# Teensy_board.net
KiCad netlist of a schematic drawn in EAGLE
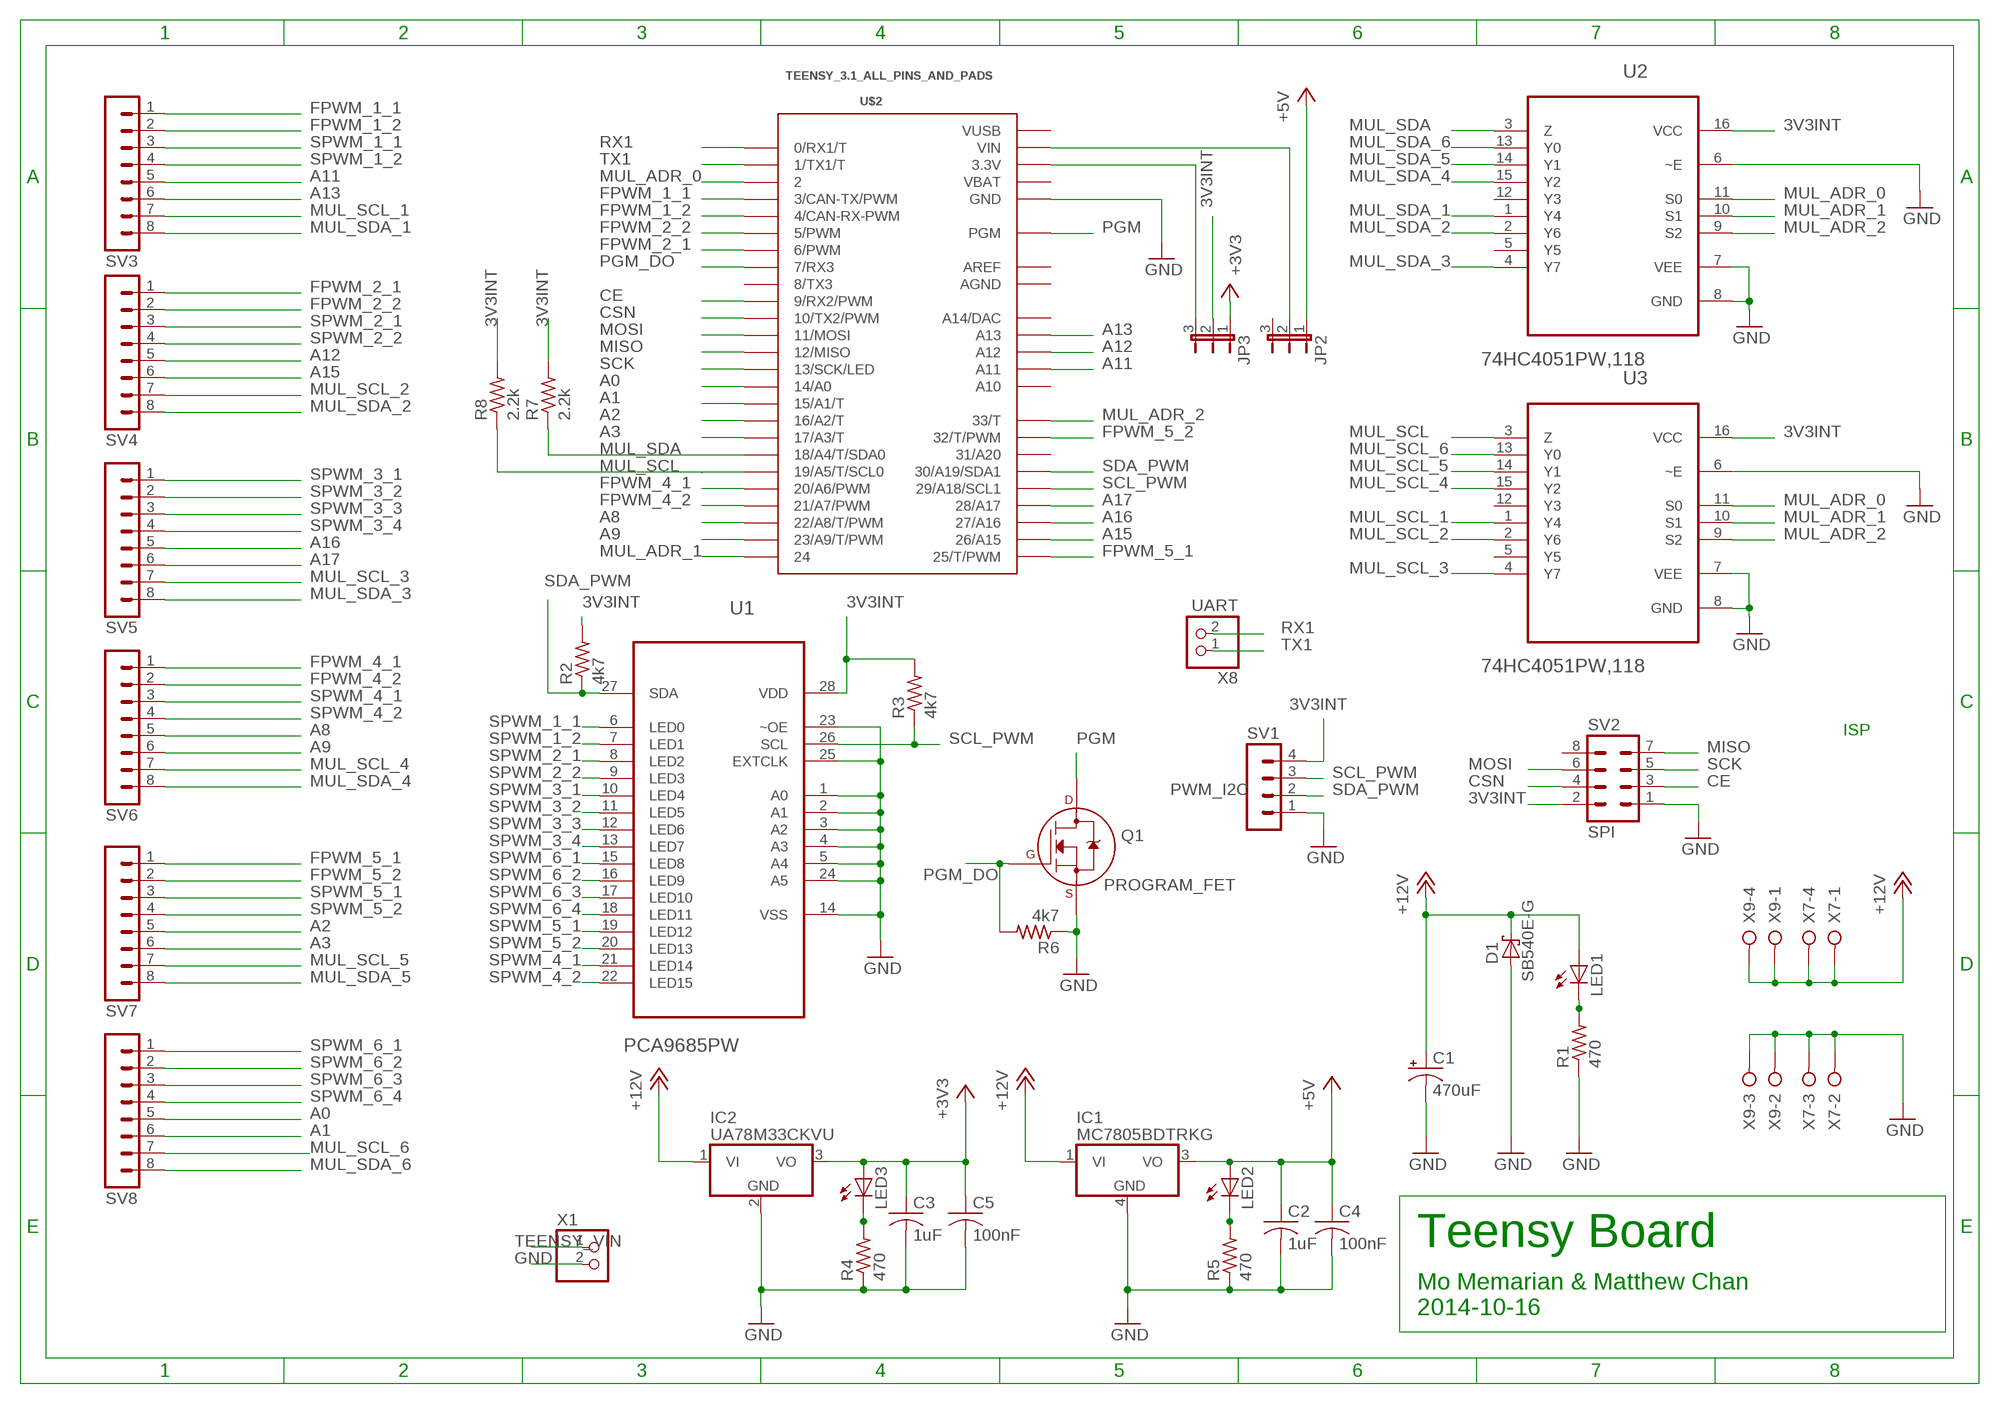
[diagram p0: schematic, sheet 1]

(export (version "E")
  (design (tool "Eeschema 10.0.6"))
  (components
    (comp (ref "C1")
      (value "470uF")
      (footprint "eagle-import:E5-10,5")
      (libsource (lib "eagle-import") (part "CPOL-USE5-10.5"))
    )
    (comp (ref "C2")
      (value "1uF")
      (footprint "eagle-import:C0603")
      (libsource (lib "eagle-import") (part "C-USC0603"))
    )
    (comp (ref "C3")
      (value "1uF")
      (footprint "eagle-import:C0603")
      (libsource (lib "eagle-import") (part "C-USC0603"))
    )
    (comp (ref "C4")
      (value "100nF")
      (footprint "eagle-import:C0603")
      (libsource (lib "eagle-import") (part "C-USC0603"))
    )
    (comp (ref "C5")
      (value "100nF")
      (footprint "eagle-import:C0603")
      (libsource (lib "eagle-import") (part "C-USC0603"))
    )
    (comp (ref "D1")
      (value "SB540E-G")
      (footprint "eagle-import:DO201T15")
      (libsource (lib "eagle-import") (part "SB540E-G"))
    )
    (comp (ref "IC1")
      (value "MC7805BDTRKG")
      (footprint "eagle-import:DPACK_3")
      (libsource (lib "eagle-import") (part "MC7805BDTRKG"))
    )
    (comp (ref "IC2")
      (value "UA78M33CKVU")
      (footprint "eagle-import:DPACK")
      (libsource (lib "eagle-import") (part "UA78MKVU33C"))
    )
    (comp (ref "JP2")
      (value "JP2E")
      (footprint "eagle-import:JP2")
      (libsource (lib "eagle-import") (part "JP2E"))
    )
    (comp (ref "JP3")
      (value "JP2E")
      (footprint "eagle-import:JP2")
      (libsource (lib "eagle-import") (part "JP2E"))
    )
    (comp (ref "LED1")
      (value "LEDSML1206")
      (footprint "eagle-import:SML1206")
      (libsource (lib "eagle-import") (part "LEDSML1206"))
    )
    (comp (ref "LED2")
      (value "LEDSML1206")
      (footprint "eagle-import:SML1206")
      (libsource (lib "eagle-import") (part "LEDSML1206"))
    )
    (comp (ref "LED3")
      (value "LEDSML1206")
      (footprint "eagle-import:SML1206")
      (libsource (lib "eagle-import") (part "LEDSML1206"))
    )
    (comp (ref "Q1")
      (value "PROGRAM_FET")
      (footprint "eagle-import:SOT-23")
      (libsource (lib "eagle-import") (part "2N700_SOT232"))
    )
    (comp (ref "R1")
      (value "470")
      (footprint "eagle-import:R0603")
      (libsource (lib "eagle-import") (part "R-US_R0603"))
    )
    (comp (ref "R2")
      (value "4k7")
      (footprint "eagle-import:R0603")
      (libsource (lib "eagle-import") (part "R-US_R0603"))
    )
    (comp (ref "R3")
      (value "4k7")
      (footprint "eagle-import:R0603")
      (libsource (lib "eagle-import") (part "R-US_R0603"))
    )
    (comp (ref "R4")
      (value "470")
      (footprint "eagle-import:R0603")
      (libsource (lib "eagle-import") (part "R-US_R0603"))
    )
    (comp (ref "R5")
      (value "470")
      (footprint "eagle-import:R0603")
      (libsource (lib "eagle-import") (part "R-US_R0603"))
    )
    (comp (ref "R6")
      (value "4k7")
      (footprint "eagle-import:R0603")
      (libsource (lib "eagle-import") (part "R-US_R0603"))
    )
    (comp (ref "R7")
      (value "2.2k")
      (footprint "eagle-import:R0603")
      (libsource (lib "eagle-import") (part "R-US_R0603"))
    )
    (comp (ref "R8")
      (value "2.2k")
      (footprint "eagle-import:R0603")
      (libsource (lib "eagle-import") (part "R-US_R0603"))
    )
    (comp (ref "SV1")
      (value "PWM_I2C")
      (footprint "eagle-import:MA04-1")
      (libsource (lib "eagle-import") (part "MA04-1"))
    )
    (comp (ref "SV2")
      (value "SPI")
      (footprint "eagle-import:MA04-2")
      (libsource (lib "eagle-import") (part "MA04-2"))
    )
    (comp (ref "SV3")
      (value "MA08-1")
      (footprint "eagle-import:MA08-1")
      (libsource (lib "eagle-import") (part "MA08-1"))
    )
    (comp (ref "SV4")
      (value "MA08-1")
      (footprint "eagle-import:MA08-1")
      (libsource (lib "eagle-import") (part "MA08-1"))
    )
    (comp (ref "SV5")
      (value "MA08-1")
      (footprint "eagle-import:MA08-1")
      (libsource (lib "eagle-import") (part "MA08-1"))
    )
    (comp (ref "SV6")
      (value "MA08-1")
      (footprint "eagle-import:MA08-1")
      (libsource (lib "eagle-import") (part "MA08-1"))
    )
    (comp (ref "SV7")
      (value "MA08-1")
      (footprint "eagle-import:MA08-1")
      (libsource (lib "eagle-import") (part "MA08-1"))
    )
    (comp (ref "SV8")
      (value "MA08-1")
      (footprint "eagle-import:MA08-1")
      (libsource (lib "eagle-import") (part "MA08-1"))
    )
    (comp (ref "U$2")
      (value "TEENSY_3.1_ALL_PINS_AND_PADS")
      (footprint "eagle-import:TEENSY_3.1_ALLPINS")
      (libsource (lib "eagle-import") (part "TEENSY_3.1_ALL_PINS_AND_PADS"))
    )
    (comp (ref "U1")
      (value "PCA9685PW")
      (footprint "eagle-import:SOP65P640X110-28N")
      (libsource (lib "eagle-import") (part "PCA9685PW"))
    )
    (comp (ref "U2")
      (value "74HC4051PW,118")
      (footprint "eagle-import:SOP65P640X110-16N")
      (libsource (lib "eagle-import") (part "74HC4051PW,118"))
    )
    (comp (ref "U3")
      (value "74HC4051PW,118")
      (footprint "eagle-import:SOP65P640X110-16N")
      (libsource (lib "eagle-import") (part "74HC4051PW,118"))
    )
    (comp (ref "X1")
      (value "PINHD-1X2")
      (footprint "eagle-import:1X02")
      (libsource (lib "eagle-import") (part "PINHD-1X2"))
    )
    (comp (ref "X7")
      (value "W237-04P")
      (footprint "eagle-import:W237-4P")
      (libsource (lib "eagle-import") (part "W237-04P"))
    )
    (comp (ref "X8")
      (value "UART")
      (footprint "eagle-import:1X02")
      (libsource (lib "eagle-import") (part "PINHD-1X2"))
    )
    (comp (ref "X9")
      (value "W237-04P")
      (footprint "eagle-import:W237-4P")
      (libsource (lib "eagle-import") (part "W237-04P"))
    )
  )
  (nets
    (net (code "1") (name "+3V3") (class "Default")
      (node (ref "C3") (pin "1") (pinfunction "1_1") (pintype "passive"))
      (node (ref "C5") (pin "1") (pinfunction "1_1") (pintype "passive"))
      (node (ref "IC2") (pin "3") (pinfunction "VO_3") (pintype "passive"))
      (node (ref "JP3") (pin "1") (pinfunction "1_1") (pintype "passive"))
      (node (ref "LED3") (pin "A") (pinfunction "A_A") (pintype "passive"))
    )
    (net (code "2") (name "+5V") (class "Default")
      (node (ref "C2") (pin "1") (pinfunction "1_1") (pintype "passive"))
      (node (ref "C4") (pin "1") (pinfunction "1_1") (pintype "passive"))
      (node (ref "IC1") (pin "3") (pinfunction "VO_3") (pintype "passive"))
      (node (ref "JP2") (pin "1") (pinfunction "1_1") (pintype "passive"))
      (node (ref "LED2") (pin "A") (pinfunction "A_A") (pintype "passive"))
    )
    (net (code "3") (name "+12V") (class "Default")
      (node (ref "C1") (pin "+") (pinfunction "+_+") (pintype "passive"))
      (node (ref "D1") (pin "C") (pinfunction "C_C") (pintype "passive"))
      (node (ref "IC1") (pin "1") (pinfunction "VI_1") (pintype "input"))
      (node (ref "IC2") (pin "1") (pinfunction "VI_1") (pintype "input"))
      (node (ref "LED1") (pin "A") (pinfunction "A_A") (pintype "passive"))
      (node (ref "X7") (pin "1") (pinfunction "KL_1") (pintype "passive"))
      (node (ref "X7") (pin "4") (pinfunction "KL_4") (pintype "passive"))
      (node (ref "X9") (pin "1") (pinfunction "KL_1") (pintype "passive"))
      (node (ref "X9") (pin "4") (pinfunction "KL_4") (pintype "passive"))
    )
    (net (code "4") (name "/3V3INT") (class "Default")
      (node (ref "JP3") (pin "2") (pinfunction "2_2") (pintype "passive"))
      (node (ref "R2") (pin "2") (pinfunction "2_2") (pintype "passive"))
      (node (ref "R3") (pin "2") (pinfunction "2_2") (pintype "passive"))
      (node (ref "R7") (pin "2") (pinfunction "2_2") (pintype "passive"))
      (node (ref "R8") (pin "2") (pinfunction "2_2") (pintype "passive"))
      (node (ref "SV1") (pin "4") (pinfunction "4_4") (pintype "passive"))
      (node (ref "SV2") (pin "2") (pinfunction "2_2") (pintype "passive"))
      (node (ref "U1") (pin "28") (pinfunction "VDD_28") (pintype "power_in"))
      (node (ref "U2") (pin "16") (pinfunction "VCC_16") (pintype "power_in"))
      (node (ref "U3") (pin "16") (pinfunction "VCC_16") (pintype "power_in"))
    )
    (net (code "5") (name "/A0") (class "Default")
      (node (ref "SV8") (pin "5") (pinfunction "5_5") (pintype "passive"))
      (node (ref "U$2") (pin "14/A0") (pinfunction "14/A0_14/A0") (pintype "bidirectional"))
    )
    (net (code "6") (name "/A1") (class "Default")
      (node (ref "SV8") (pin "6") (pinfunction "6_6") (pintype "passive"))
      (node (ref "U$2") (pin "15/A1") (pinfunction "15/A1/T_15/A1") (pintype "bidirectional"))
    )
    (net (code "7") (name "/A2") (class "Default")
      (node (ref "SV7") (pin "5") (pinfunction "5_5") (pintype "passive"))
      (node (ref "U$2") (pin "16/A2") (pinfunction "16/A2/T_16/A2") (pintype "bidirectional"))
    )
    (net (code "8") (name "/A3") (class "Default")
      (node (ref "SV7") (pin "6") (pinfunction "6_6") (pintype "passive"))
      (node (ref "U$2") (pin "17/A3") (pinfunction "17/A3/T_17/A3") (pintype "bidirectional"))
    )
    (net (code "9") (name "/A8") (class "Default")
      (node (ref "SV6") (pin "5") (pinfunction "5_5") (pintype "passive"))
      (node (ref "U$2") (pin "22/A8") (pinfunction "22/A8/T/PWM_22/A8") (pintype "bidirectional"))
    )
    (net (code "10") (name "/A9") (class "Default")
      (node (ref "SV6") (pin "6") (pinfunction "6_6") (pintype "passive"))
      (node (ref "U$2") (pin "23/A9") (pinfunction "23/A9/T/PWM_23/A9") (pintype "bidirectional"))
    )
    (net (code "11") (name "/A11") (class "Default")
      (node (ref "SV3") (pin "5") (pinfunction "5_5") (pintype "passive"))
      (node (ref "U$2") (pin "A11") (pinfunction "A11_A11") (pintype "bidirectional"))
    )
    (net (code "12") (name "/A12") (class "Default")
      (node (ref "SV4") (pin "5") (pinfunction "5_5") (pintype "passive"))
      (node (ref "U$2") (pin "A12") (pinfunction "A12_A12") (pintype "bidirectional"))
    )
    (net (code "13") (name "/A13") (class "Default")
      (node (ref "SV3") (pin "6") (pinfunction "6_6") (pintype "passive"))
      (node (ref "U$2") (pin "A13") (pinfunction "A13_A13") (pintype "bidirectional"))
    )
    (net (code "14") (name "/A15") (class "Default")
      (node (ref "SV4") (pin "6") (pinfunction "6_6") (pintype "passive"))
      (node (ref "U$2") (pin "26") (pinfunction "26/A15_26") (pintype "bidirectional"))
    )
    (net (code "15") (name "/A16") (class "Default")
      (node (ref "SV5") (pin "5") (pinfunction "5_5") (pintype "passive"))
      (node (ref "U$2") (pin "27") (pinfunction "27/A16_27") (pintype "bidirectional"))
    )
    (net (code "16") (name "/A17") (class "Default")
      (node (ref "SV5") (pin "6") (pinfunction "6_6") (pintype "passive"))
      (node (ref "U$2") (pin "28") (pinfunction "28/A17_28") (pintype "bidirectional"))
    )
    (net (code "17") (name "/AGND") (class "Default")
      (node (ref "U$2") (pin "AGND") (pinfunction "AGND_AGND") (pintype "power_in"))
    )
    (net (code "18") (name "/AREF") (class "Default")
      (node (ref "U$2") (pin "AREF") (pinfunction "AREF_AREF") (pintype "power_in"))
    )
    (net (code "19") (name "/CE") (class "Default")
      (node (ref "SV2") (pin "3") (pinfunction "3_3") (pintype "passive"))
      (node (ref "U$2") (pin "9") (pinfunction "9/RX2/PWM_9") (pintype "bidirectional"))
    )
    (net (code "20") (name "/CSN") (class "Default")
      (node (ref "SV2") (pin "4") (pinfunction "4_4") (pintype "passive"))
      (node (ref "U$2") (pin "10") (pinfunction "10/TX2/PWM_10") (pintype "bidirectional"))
    )
    (net (code "21") (name "/FPWM_1_1") (class "Default")
      (node (ref "SV3") (pin "1") (pinfunction "1_1") (pintype "passive"))
      (node (ref "U$2") (pin "3") (pinfunction "3/CAN-TX/PWM_3") (pintype "bidirectional"))
    )
    (net (code "22") (name "/FPWM_1_2") (class "Default")
      (node (ref "SV3") (pin "2") (pinfunction "2_2") (pintype "passive"))
      (node (ref "U$2") (pin "4") (pinfunction "4/CAN-RX-PWM_4") (pintype "bidirectional"))
    )
    (net (code "23") (name "/FPWM_2_1") (class "Default")
      (node (ref "SV4") (pin "1") (pinfunction "1_1") (pintype "passive"))
      (node (ref "U$2") (pin "6") (pinfunction "6/PWM_6") (pintype "bidirectional"))
    )
    (net (code "24") (name "/FPWM_2_2") (class "Default")
      (node (ref "SV4") (pin "2") (pinfunction "2_2") (pintype "passive"))
      (node (ref "U$2") (pin "5") (pinfunction "5/PWM_5") (pintype "bidirectional"))
    )
    (net (code "25") (name "/FPWM_4_1") (class "Default")
      (node (ref "SV6") (pin "1") (pinfunction "1_1") (pintype "passive"))
      (node (ref "U$2") (pin "20/A6") (pinfunction "20/A6/PWM_20/A6") (pintype "bidirectional"))
    )
    (net (code "26") (name "/FPWM_4_2") (class "Default")
      (node (ref "SV6") (pin "2") (pinfunction "2_2") (pintype "passive"))
      (node (ref "U$2") (pin "21/A7") (pinfunction "21/A7/PWM_21/A7") (pintype "bidirectional"))
    )
    (net (code "27") (name "/FPWM_5_1") (class "Default")
      (node (ref "SV7") (pin "1") (pinfunction "1_1") (pintype "passive"))
      (node (ref "U$2") (pin "25") (pinfunction "25/T/PWM_25") (pintype "bidirectional"))
    )
    (net (code "28") (name "/FPWM_5_2") (class "Default")
      (node (ref "SV7") (pin "2") (pinfunction "2_2") (pintype "passive"))
      (node (ref "U$2") (pin "32") (pinfunction "32/T/PWM_32") (pintype "bidirectional"))
    )
    (net (code "29") (name "/MISO") (class "Default")
      (node (ref "SV2") (pin "7") (pinfunction "7_7") (pintype "passive"))
      (node (ref "U$2") (pin "12") (pinfunction "12/MISO_12") (pintype "bidirectional"))
    )
    (net (code "30") (name "/MOSI") (class "Default")
      (node (ref "SV2") (pin "6") (pinfunction "6_6") (pintype "passive"))
      (node (ref "U$2") (pin "11") (pinfunction "11/MOSI_11") (pintype "bidirectional"))
    )
    (net (code "31") (name "/MUL_ADR_0") (class "Default")
      (node (ref "U$2") (pin "2") (pinfunction "2_2") (pintype "bidirectional"))
      (node (ref "U2") (pin "11") (pinfunction "S0_11") (pintype "input"))
      (node (ref "U3") (pin "11") (pinfunction "S0_11") (pintype "input"))
    )
    (net (code "32") (name "/MUL_ADR_1") (class "Default")
      (node (ref "U$2") (pin "24") (pinfunction "24_24") (pintype "bidirectional"))
      (node (ref "U2") (pin "10") (pinfunction "S1_10") (pintype "input"))
      (node (ref "U3") (pin "10") (pinfunction "S1_10") (pintype "input"))
    )
    (net (code "33") (name "/MUL_ADR_2") (class "Default")
      (node (ref "U$2") (pin "33") (pinfunction "33/T_33") (pintype "bidirectional"))
      (node (ref "U2") (pin "9") (pinfunction "S2_9") (pintype "input"))
      (node (ref "U3") (pin "9") (pinfunction "S2_9") (pintype "input"))
    )
    (net (code "34") (name "/MUL_SCL") (class "Default")
      (node (ref "R8") (pin "1") (pinfunction "1_1") (pintype "passive"))
      (node (ref "U$2") (pin "19/A5") (pinfunction "19/A5/T/SCL0_19/A5") (pintype "bidirectional"))
      (node (ref "U3") (pin "3") (pinfunction "Z_3") (pintype "bidirectional"))
    )
    (net (code "35") (name "/MUL_SCL_1") (class "Default")
      (node (ref "SV3") (pin "7") (pinfunction "7_7") (pintype "passive"))
      (node (ref "U3") (pin "1") (pinfunction "Y4_1") (pintype "bidirectional"))
    )
    (net (code "36") (name "/MUL_SCL_2") (class "Default")
      (node (ref "SV4") (pin "7") (pinfunction "7_7") (pintype "passive"))
      (node (ref "U3") (pin "2") (pinfunction "Y6_2") (pintype "bidirectional"))
    )
    (net (code "37") (name "/MUL_SCL_3") (class "Default")
      (node (ref "SV5") (pin "7") (pinfunction "7_7") (pintype "passive"))
      (node (ref "U3") (pin "4") (pinfunction "Y7_4") (pintype "bidirectional"))
    )
    (net (code "38") (name "/MUL_SCL_4") (class "Default")
      (node (ref "SV6") (pin "7") (pinfunction "7_7") (pintype "passive"))
      (node (ref "U3") (pin "15") (pinfunction "Y2_15") (pintype "bidirectional"))
    )
    (net (code "39") (name "/MUL_SCL_5") (class "Default")
      (node (ref "SV7") (pin "7") (pinfunction "7_7") (pintype "passive"))
      (node (ref "U3") (pin "14") (pinfunction "Y1_14") (pintype "bidirectional"))
    )
    (net (code "40") (name "/MUL_SCL_6") (class "Default")
      (node (ref "SV8") (pin "7") (pinfunction "7_7") (pintype "passive"))
      (node (ref "U3") (pin "13") (pinfunction "Y0_13") (pintype "bidirectional"))
    )
    (net (code "41") (name "/MUL_SDA") (class "Default")
      (node (ref "R7") (pin "1") (pinfunction "1_1") (pintype "passive"))
      (node (ref "U$2") (pin "18/A4") (pinfunction "18/A4/T/SDA0_18/A4") (pintype "bidirectional"))
      (node (ref "U2") (pin "3") (pinfunction "Z_3") (pintype "bidirectional"))
    )
    (net (code "42") (name "/MUL_SDA_1") (class "Default")
      (node (ref "SV3") (pin "8") (pinfunction "8_8") (pintype "passive"))
      (node (ref "U2") (pin "1") (pinfunction "Y4_1") (pintype "bidirectional"))
    )
    (net (code "43") (name "/MUL_SDA_2") (class "Default")
      (node (ref "SV4") (pin "8") (pinfunction "8_8") (pintype "passive"))
      (node (ref "U2") (pin "2") (pinfunction "Y6_2") (pintype "bidirectional"))
    )
    (net (code "44") (name "/MUL_SDA_3") (class "Default")
      (node (ref "SV5") (pin "8") (pinfunction "8_8") (pintype "passive"))
      (node (ref "U2") (pin "4") (pinfunction "Y7_4") (pintype "bidirectional"))
    )
    (net (code "45") (name "/MUL_SDA_4") (class "Default")
      (node (ref "SV6") (pin "8") (pinfunction "8_8") (pintype "passive"))
      (node (ref "U2") (pin "15") (pinfunction "Y2_15") (pintype "bidirectional"))
    )
    (net (code "46") (name "/MUL_SDA_5") (class "Default")
      (node (ref "SV7") (pin "8") (pinfunction "8_8") (pintype "passive"))
      (node (ref "U2") (pin "14") (pinfunction "Y1_14") (pintype "bidirectional"))
    )
    (net (code "47") (name "/MUL_SDA_6") (class "Default")
      (node (ref "SV8") (pin "8") (pinfunction "8_8") (pintype "passive"))
      (node (ref "U2") (pin "13") (pinfunction "Y0_13") (pintype "bidirectional"))
    )
    (net (code "48") (name "/PGM") (class "Default")
      (node (ref "Q1") (pin "3") (pinfunction "D_3") (pintype "bidirectional"))
      (node (ref "U$2") (pin "PGM") (pinfunction "PGM_PGM") (pintype "bidirectional"))
    )
    (net (code "49") (name "/PGM_DO") (class "Default")
      (node (ref "Q1") (pin "1") (pinfunction "G_1") (pintype "tri_state"))
      (node (ref "R6") (pin "2") (pinfunction "2_2") (pintype "passive"))
      (node (ref "U$2") (pin "7") (pinfunction "7/RX3_7") (pintype "bidirectional"))
    )
    (net (code "50") (name "/RX1") (class "Default")
      (node (ref "U$2") (pin "0") (pinfunction "0/RX1/T_0") (pintype "bidirectional"))
      (node (ref "X8") (pin "2") (pinfunction "2_2") (pintype "passive"))
    )
    (net (code "51") (name "/SCK") (class "Default")
      (node (ref "SV2") (pin "5") (pinfunction "5_5") (pintype "passive"))
      (node (ref "U$2") (pin "13") (pinfunction "13/SCK/LED_13") (pintype "bidirectional"))
    )
    (net (code "52") (name "/SCL_PWM") (class "Default")
      (node (ref "R3") (pin "1") (pinfunction "1_1") (pintype "passive"))
      (node (ref "SV1") (pin "3") (pinfunction "3_3") (pintype "passive"))
      (node (ref "U$2") (pin "29") (pinfunction "29/A18/SCL1_29") (pintype "bidirectional"))
      (node (ref "U1") (pin "26") (pinfunction "SCL_26") (pintype "input"))
    )
    (net (code "53") (name "/SDA_PWM") (class "Default")
      (node (ref "R2") (pin "1") (pinfunction "1_1") (pintype "passive"))
      (node (ref "SV1") (pin "2") (pinfunction "2_2") (pintype "passive"))
      (node (ref "U$2") (pin "30") (pinfunction "30/A19/SDA1_30") (pintype "bidirectional"))
      (node (ref "U1") (pin "27") (pinfunction "SDA_27") (pintype "bidirectional"))
    )
    (net (code "54") (name "/SPWM_1_1") (class "Default")
      (node (ref "SV3") (pin "3") (pinfunction "3_3") (pintype "passive"))
      (node (ref "U1") (pin "6") (pinfunction "LED0_6") (pintype "output"))
    )
    (net (code "55") (name "/SPWM_1_2") (class "Default")
      (node (ref "SV3") (pin "4") (pinfunction "4_4") (pintype "passive"))
      (node (ref "U1") (pin "7") (pinfunction "LED1_7") (pintype "output"))
    )
    (net (code "56") (name "/SPWM_2_1") (class "Default")
      (node (ref "SV4") (pin "3") (pinfunction "3_3") (pintype "passive"))
      (node (ref "U1") (pin "8") (pinfunction "LED2_8") (pintype "output"))
    )
    (net (code "57") (name "/SPWM_2_2") (class "Default")
      (node (ref "SV4") (pin "4") (pinfunction "4_4") (pintype "passive"))
      (node (ref "U1") (pin "9") (pinfunction "LED3_9") (pintype "output"))
    )
    (net (code "58") (name "/SPWM_3_1") (class "Default")
      (node (ref "SV5") (pin "1") (pinfunction "1_1") (pintype "passive"))
      (node (ref "U1") (pin "10") (pinfunction "LED4_10") (pintype "output"))
    )
    (net (code "59") (name "/SPWM_3_2") (class "Default")
      (node (ref "SV5") (pin "2") (pinfunction "2_2") (pintype "passive"))
      (node (ref "U1") (pin "11") (pinfunction "LED5_11") (pintype "output"))
    )
    (net (code "60") (name "/SPWM_3_3") (class "Default")
      (node (ref "SV5") (pin "3") (pinfunction "3_3") (pintype "passive"))
      (node (ref "U1") (pin "12") (pinfunction "LED6_12") (pintype "output"))
    )
    (net (code "61") (name "/SPWM_3_4") (class "Default")
      (node (ref "SV5") (pin "4") (pinfunction "4_4") (pintype "passive"))
      (node (ref "U1") (pin "13") (pinfunction "LED7_13") (pintype "output"))
    )
    (net (code "62") (name "/SPWM_4_1") (class "Default")
      (node (ref "SV6") (pin "3") (pinfunction "3_3") (pintype "passive"))
      (node (ref "U1") (pin "21") (pinfunction "LED14_21") (pintype "output"))
    )
    (net (code "63") (name "/SPWM_4_2") (class "Default")
      (node (ref "SV6") (pin "4") (pinfunction "4_4") (pintype "passive"))
      (node (ref "U1") (pin "22") (pinfunction "LED15_22") (pintype "output"))
    )
    (net (code "64") (name "/SPWM_5_1") (class "Default")
      (node (ref "SV7") (pin "3") (pinfunction "3_3") (pintype "passive"))
      (node (ref "U1") (pin "19") (pinfunction "LED12_19") (pintype "output"))
    )
    (net (code "65") (name "/SPWM_5_2") (class "Default")
      (node (ref "SV7") (pin "4") (pinfunction "4_4") (pintype "passive"))
      (node (ref "U1") (pin "20") (pinfunction "LED13_20") (pintype "output"))
    )
    (net (code "66") (name "/SPWM_6_1") (class "Default")
      (node (ref "SV8") (pin "1") (pinfunction "1_1") (pintype "passive"))
      (node (ref "U1") (pin "15") (pinfunction "LED8_15") (pintype "output"))
    )
    (net (code "67") (name "/SPWM_6_2") (class "Default")
      (node (ref "SV8") (pin "2") (pinfunction "2_2") (pintype "passive"))
      (node (ref "U1") (pin "16") (pinfunction "LED9_16") (pintype "output"))
    )
    (net (code "68") (name "/SPWM_6_3") (class "Default")
      (node (ref "SV8") (pin "3") (pinfunction "3_3") (pintype "passive"))
      (node (ref "U1") (pin "17") (pinfunction "LED10_17") (pintype "output"))
    )
    (net (code "69") (name "/SPWM_6_4") (class "Default")
      (node (ref "SV8") (pin "4") (pinfunction "4_4") (pintype "passive"))
      (node (ref "U1") (pin "18") (pinfunction "LED11_18") (pintype "output"))
    )
    (net (code "70") (name "/TEENSY_VIN") (class "Default")
      (node (ref "JP2") (pin "2") (pinfunction "2_2") (pintype "passive"))
      (node (ref "U$2") (pin "VIN") (pinfunction "VIN_VIN") (pintype "power_in"))
      (node (ref "X1") (pin "1") (pinfunction "1_1") (pintype "passive"))
    )
    (net (code "71") (name "/TX1") (class "Default")
      (node (ref "U$2") (pin "1") (pinfunction "1/TX1/T_1") (pintype "bidirectional"))
      (node (ref "X8") (pin "1") (pinfunction "1_1") (pintype "passive"))
    )
    (net (code "72") (name "/VBAT") (class "Default")
      (node (ref "U$2") (pin "VBAT") (pinfunction "VBAT_VBAT") (pintype "power_in"))
    )
    (net (code "73") (name "/VUSB") (class "Default")
      (node (ref "U$2") (pin "VUSB") (pinfunction "VUSB_VUSB") (pintype "power_in"))
    )
    (net (code "74") (name "GND") (class "Default")
      (node (ref "C1") (pin "-") (pinfunction "-_-") (pintype "passive"))
      (node (ref "C2") (pin "2") (pinfunction "2_2") (pintype "passive"))
      (node (ref "C3") (pin "2") (pinfunction "2_2") (pintype "passive"))
      (node (ref "C4") (pin "2") (pinfunction "2_2") (pintype "passive"))
      (node (ref "C5") (pin "2") (pinfunction "2_2") (pintype "passive"))
      (node (ref "D1") (pin "A") (pinfunction "A_A") (pintype "passive"))
      (node (ref "IC1") (pin "4") (pinfunction "GND_4") (pintype "passive"))
      (node (ref "IC2") (pin "2") (pinfunction "GND_2") (pintype "passive"))
      (node (ref "Q1") (pin "2") (pinfunction "S_2") (pintype "bidirectional"))
      (node (ref "R1") (pin "1") (pinfunction "1_1") (pintype "passive"))
      (node (ref "R4") (pin "1") (pinfunction "1_1") (pintype "passive"))
      (node (ref "R5") (pin "1") (pinfunction "1_1") (pintype "passive"))
      (node (ref "R6") (pin "1") (pinfunction "1_1") (pintype "passive"))
      (node (ref "SV1") (pin "1") (pinfunction "1_1") (pintype "passive"))
      (node (ref "SV2") (pin "1") (pinfunction "1_1") (pintype "passive"))
      (node (ref "U$2") (pin "GND") (pinfunction "GND_GND") (pintype "power_in"))
      (node (ref "U$2") (pin "GND1") (pinfunction "GND_GND1") (pintype "power_in"))
      (node (ref "U$2") (pin "GND2") (pinfunction "GND_GND2") (pintype "power_in"))
      (node (ref "U1") (pin "1") (pinfunction "A0_1") (pintype "input"))
      (node (ref "U1") (pin "14") (pinfunction "VSS_14") (pintype "passive"))
      (node (ref "U1") (pin "2") (pinfunction "A1_2") (pintype "input"))
      (node (ref "U1") (pin "23") (pinfunction "~{OE}_23") (pintype "input"))
      (node (ref "U1") (pin "24") (pinfunction "A5_24") (pintype "input"))
      (node (ref "U1") (pin "25") (pinfunction "EXTCLK_25") (pintype "input"))
      (node (ref "U1") (pin "3") (pinfunction "A2_3") (pintype "input"))
      (node (ref "U1") (pin "4") (pinfunction "A3_4") (pintype "input"))
      (node (ref "U1") (pin "5") (pinfunction "A4_5") (pintype "input"))
      (node (ref "U2") (pin "6") (pinfunction "~{E}_6") (pintype "input"))
      (node (ref "U2") (pin "7") (pinfunction "VEE_7") (pintype "power_in"))
      (node (ref "U2") (pin "8") (pinfunction "GND_8") (pintype "passive"))
      (node (ref "U3") (pin "6") (pinfunction "~{E}_6") (pintype "input"))
      (node (ref "U3") (pin "7") (pinfunction "VEE_7") (pintype "power_in"))
      (node (ref "U3") (pin "8") (pinfunction "GND_8") (pintype "passive"))
      (node (ref "X1") (pin "2") (pinfunction "2_2") (pintype "passive"))
      (node (ref "X7") (pin "2") (pinfunction "KL_2") (pintype "passive"))
      (node (ref "X7") (pin "3") (pinfunction "KL_3") (pintype "passive"))
      (node (ref "X9") (pin "2") (pinfunction "KL_2") (pintype "passive"))
      (node (ref "X9") (pin "3") (pinfunction "KL_3") (pintype "passive"))
    )
    (net (code "75") (name "Net-(JP3-Pad3)") (class "Default")
      (node (ref "JP3") (pin "3") (pinfunction "3_3") (pintype "passive"))
      (node (ref "U$2") (pin "3.3V") (pinfunction "3.3V_3.3V") (pintype "power_in"))
      (node (ref "U$2") (pin "3.3V1") (pinfunction "3.3V_3.3V1") (pintype "power_in"))
      (node (ref "U$2") (pin "3.3V2") (pinfunction "3.3V_3.3V2") (pintype "power_in"))
    )
    (net (code "76") (name "Net-(LED1-PadC)") (class "Default")
      (node (ref "LED1") (pin "C") (pinfunction "C_C") (pintype "passive"))
      (node (ref "R1") (pin "2") (pinfunction "2_2") (pintype "passive"))
    )
    (net (code "77") (name "Net-(LED2-PadC)") (class "Default")
      (node (ref "LED2") (pin "C") (pinfunction "C_C") (pintype "passive"))
      (node (ref "R5") (pin "2") (pinfunction "2_2") (pintype "passive"))
    )
    (net (code "78") (name "Net-(LED3-PadC)") (class "Default")
      (node (ref "LED3") (pin "C") (pinfunction "C_C") (pintype "passive"))
      (node (ref "R4") (pin "2") (pinfunction "2_2") (pintype "passive"))
    )
    (net (code "79") (name "unconnected-(JP2-Pad3)") (class "Default")
      (node (ref "JP2") (pin "3") (pinfunction "3_3") (pintype "passive"))
    )
    (net (code "80") (name "unconnected-(SV2-Pad8)") (class "Default")
      (node (ref "SV2") (pin "8") (pinfunction "8_8") (pintype "passive"))
    )
    (net (code "81") (name "unconnected-(U$2-8{slash}TX3-Pad8)") (class "Default")
      (node (ref "U$2") (pin "8") (pinfunction "8/TX3_8") (pintype "bidirectional"))
    )
    (net (code "82") (name "unconnected-(U$2-31{slash}A20-Pad31)") (class "Default")
      (node (ref "U$2") (pin "31") (pinfunction "31/A20_31") (pintype "bidirectional"))
    )
    (net (code "83") (name "unconnected-(U$2-A14{slash}DAC-PadA14)") (class "Default")
      (node (ref "U$2") (pin "A14") (pinfunction "A14/DAC_A14") (pintype "bidirectional"))
    )
    (net (code "84") (name "unconnected-(U$2-PadA10)") (class "Default")
      (node (ref "U$2") (pin "A10") (pinfunction "A10_A10") (pintype "bidirectional"))
    )
    (net (code "85") (name "unconnected-(U2-Y3-Pad12)") (class "Default")
      (node (ref "U2") (pin "12") (pinfunction "Y3_12") (pintype "bidirectional"))
    )
    (net (code "86") (name "unconnected-(U2-Y5-Pad5)") (class "Default")
      (node (ref "U2") (pin "5") (pinfunction "Y5_5") (pintype "bidirectional"))
    )
    (net (code "87") (name "unconnected-(U3-Y3-Pad12)") (class "Default")
      (node (ref "U3") (pin "12") (pinfunction "Y3_12") (pintype "bidirectional"))
    )
    (net (code "88") (name "unconnected-(U3-Y5-Pad5)") (class "Default")
      (node (ref "U3") (pin "5") (pinfunction "Y5_5") (pintype "bidirectional"))
    )
  )
)
